# Raspberry_output_for_PWM_based_Fan_drive.net
KiCad netlist of a schematic drawn in EAGLE
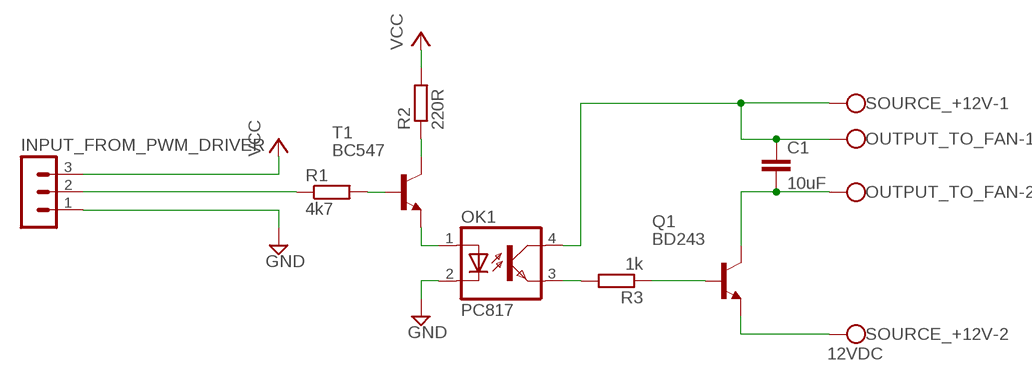
[diagram p0: schematic, sheet 1]

(export (version "E")
  (design (tool "Eeschema 10.0.6"))
  (components
    (comp (ref "C1")
      (value "10uF")
      (footprint "eagle-import:C2.5-5")
      (libsource (lib "eagle-import") (part "C2.5/5"))
    )
    (comp (ref "INPUT_FROM_PWM_DRIVER")
      (value "MA03-1")
      (footprint "eagle-import:MA03-1")
      (libsource (lib "eagle-import") (part "MA03-1"))
    )
    (comp (ref "OK1")
      (value "PC817")
      (footprint "eagle-import:DIL04")
      (libsource (lib "eagle-import") (part "PC817"))
    )
    (comp (ref "OUTPUT_TO_FAN")
      (value "W237-102")
      (footprint "eagle-import:W237-102")
      (libsource (lib "eagle-import") (part "W237-102"))
    )
    (comp (ref "Q1")
      (value "BD243")
      (footprint "eagle-import:TO220")
      (libsource (lib "eagle-import") (part "BD243"))
    )
    (comp (ref "R1")
      (value "4k7")
      (footprint "eagle-import:0207_10")
      (libsource (lib "eagle-import") (part "R-EU_0207/10"))
    )
    (comp (ref "R2")
      (value "220R")
      (footprint "eagle-import:0207_10")
      (libsource (lib "eagle-import") (part "R-EU_0207/10"))
    )
    (comp (ref "R3")
      (value "1k")
      (footprint "eagle-import:0207_10")
      (libsource (lib "eagle-import") (part "R-EU_0207/10"))
    )
    (comp (ref "SOURCE_+12V")
      (value "12VDC")
      (footprint "eagle-import:W237-102")
      (libsource (lib "eagle-import") (part "W237-102"))
    )
    (comp (ref "T1")
      (value "BC547")
      (footprint "eagle-import:TO92")
      (libsource (lib "eagle-import") (part "BC547"))
    )
  )
  (nets
    (net (code "1") (name "GND") (class "Default")
      (node (ref "INPUT_FROM_PWM_DRIVER") (pin "1") (pinfunction "1_1") (pintype "passive"))
      (node (ref "OK1") (pin "2") (pinfunction "C_2") (pintype "passive"))
    )
    (net (code "2") (name "Net-(INPUT_FROM_PWM_DRIVER-Pad2)") (class "Default")
      (node (ref "INPUT_FROM_PWM_DRIVER") (pin "2") (pinfunction "2_2") (pintype "passive"))
      (node (ref "R1") (pin "1") (pinfunction "1_1") (pintype "passive"))
    )
    (net (code "3") (name "Net-(OK1-A)") (class "Default")
      (node (ref "OK1") (pin "1") (pinfunction "A_1") (pintype "passive"))
      (node (ref "T1") (pin "1") (pinfunction "E_1") (pintype "passive"))
    )
    (net (code "4") (name "Net-(OK1-COL)") (class "Default")
      (node (ref "C1") (pin "1") (pinfunction "1_1") (pintype "passive"))
      (node (ref "OK1") (pin "4") (pinfunction "COL_4") (pintype "passive"))
      (node (ref "OUTPUT_TO_FAN") (pin "1") (pinfunction "KL_1") (pintype "passive"))
      (node (ref "SOURCE_+12V") (pin "1") (pinfunction "KL_1") (pintype "passive"))
    )
    (net (code "5") (name "Net-(OK1-EMIT)") (class "Default")
      (node (ref "OK1") (pin "3") (pinfunction "EMIT_3") (pintype "passive"))
      (node (ref "R3") (pin "2") (pinfunction "2_2") (pintype "passive"))
    )
    (net (code "6") (name "Net-(OUTPUT_TO_FANB-KL)") (class "Default")
      (node (ref "C1") (pin "2") (pinfunction "2_2") (pintype "passive"))
      (node (ref "OUTPUT_TO_FAN") (pin "2") (pinfunction "KL_2") (pintype "passive"))
      (node (ref "Q1") (pin "2") (pinfunction "C_2") (pintype "passive"))
    )
    (net (code "7") (name "Net-(Q1-B)") (class "Default")
      (node (ref "Q1") (pin "1") (pinfunction "B_1") (pintype "passive"))
      (node (ref "R3") (pin "1") (pinfunction "1_1") (pintype "passive"))
    )
    (net (code "8") (name "Net-(Q1-E)") (class "Default")
      (node (ref "Q1") (pin "3") (pinfunction "E_3") (pintype "passive"))
      (node (ref "SOURCE_+12V") (pin "2") (pinfunction "KL_2") (pintype "passive"))
    )
    (net (code "9") (name "Net-(T1-B)") (class "Default")
      (node (ref "R1") (pin "2") (pinfunction "2_2") (pintype "passive"))
      (node (ref "T1") (pin "2") (pinfunction "B_2") (pintype "passive"))
    )
    (net (code "10") (name "Net-(T1-C)") (class "Default")
      (node (ref "R2") (pin "1") (pinfunction "1_1") (pintype "passive"))
      (node (ref "T1") (pin "3") (pinfunction "C_3") (pintype "passive"))
    )
    (net (code "11") (name "VCC") (class "Default")
      (node (ref "INPUT_FROM_PWM_DRIVER") (pin "3") (pinfunction "3_3") (pintype "passive"))
      (node (ref "R2") (pin "2") (pinfunction "2_2") (pintype "passive"))
    )
  )
)
